# Microcontroller_Board.net
KiCad netlist of a schematic drawn in Altium Designer
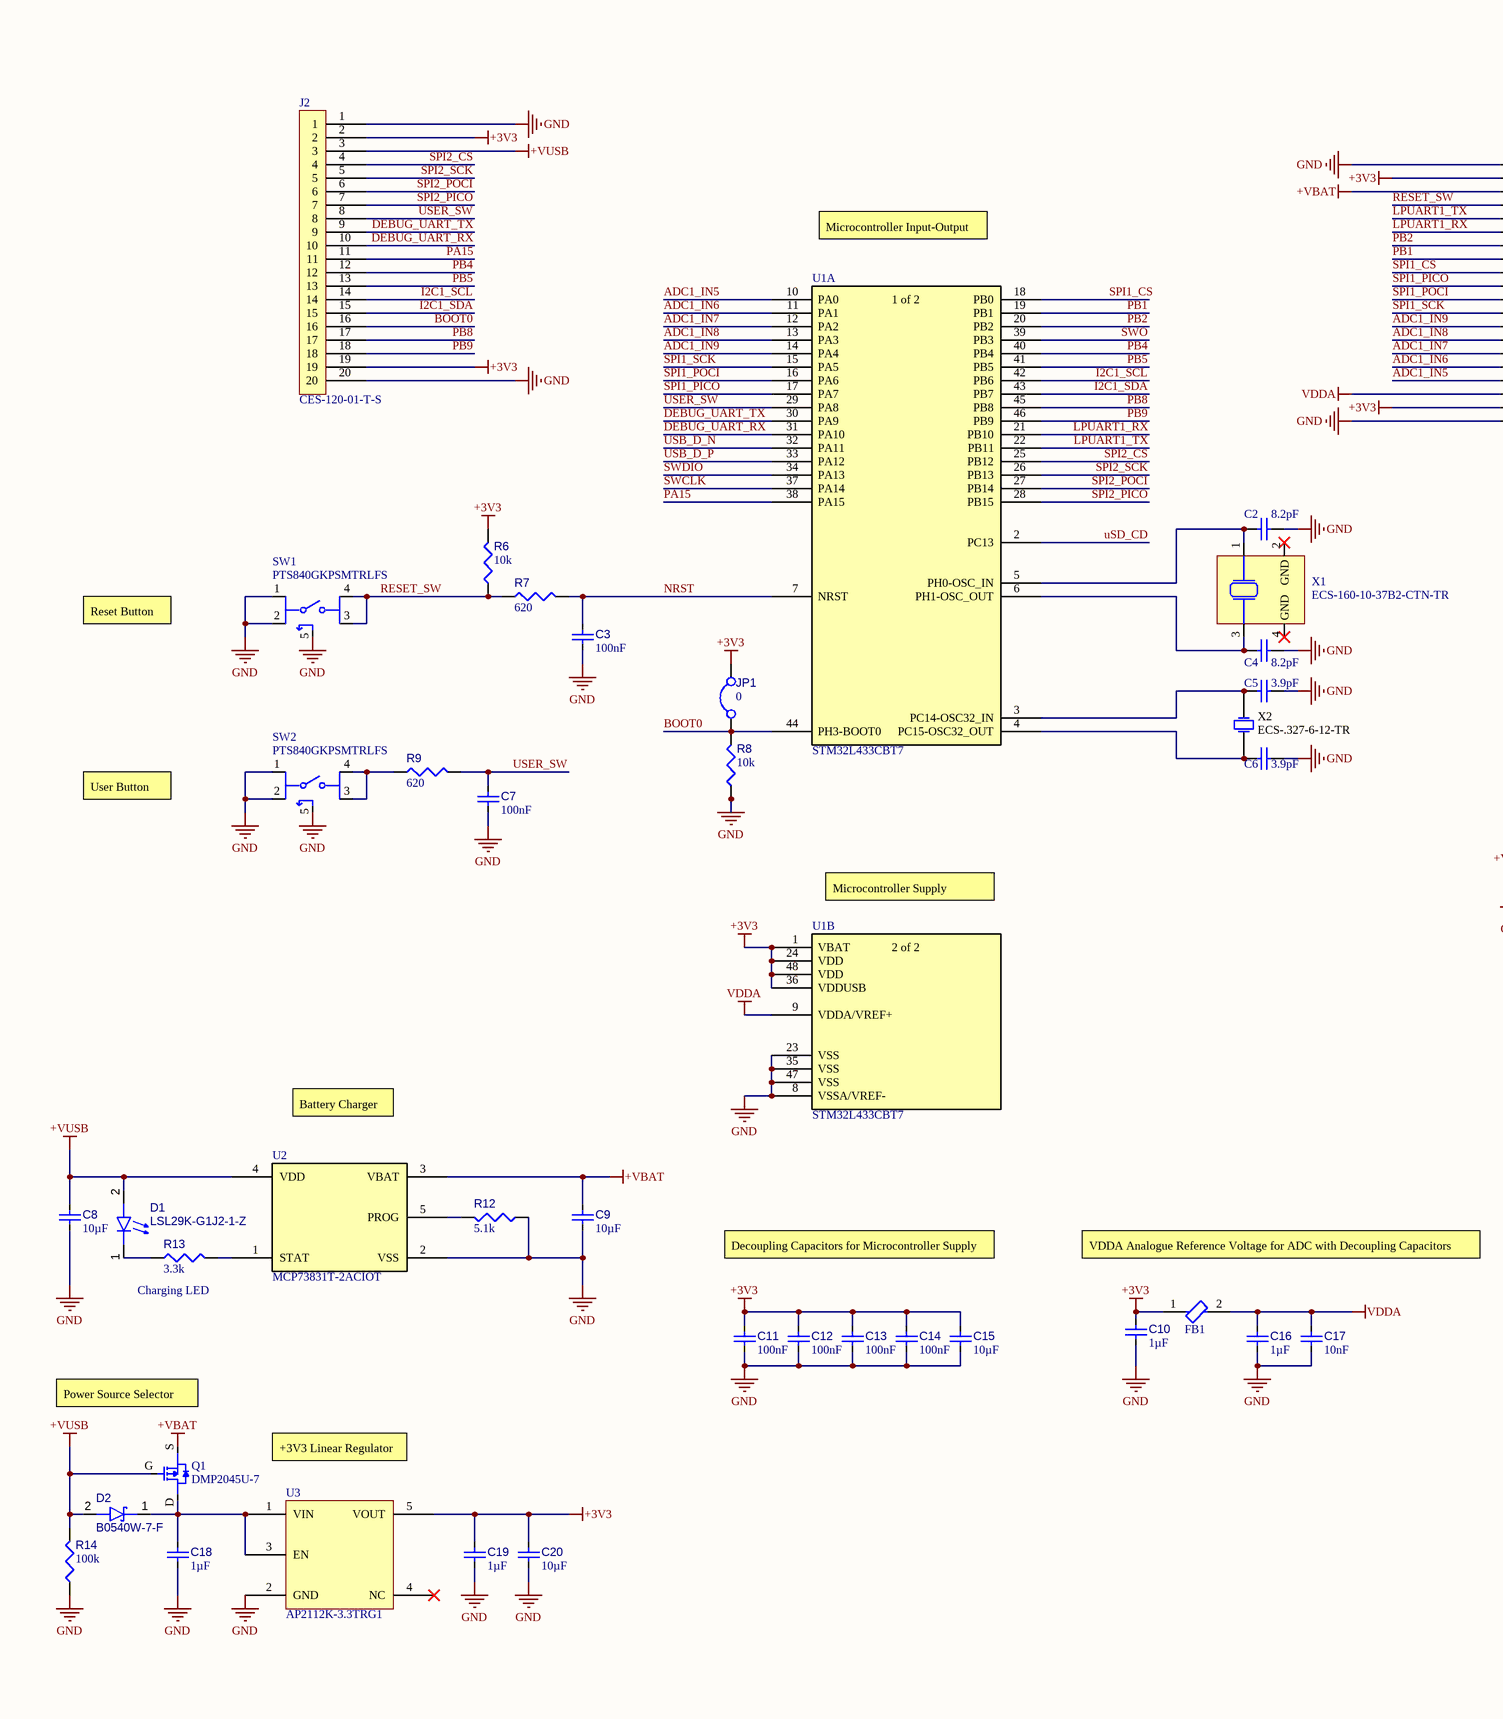
[diagram p0: Microcontroller Board.SchDoc, left]
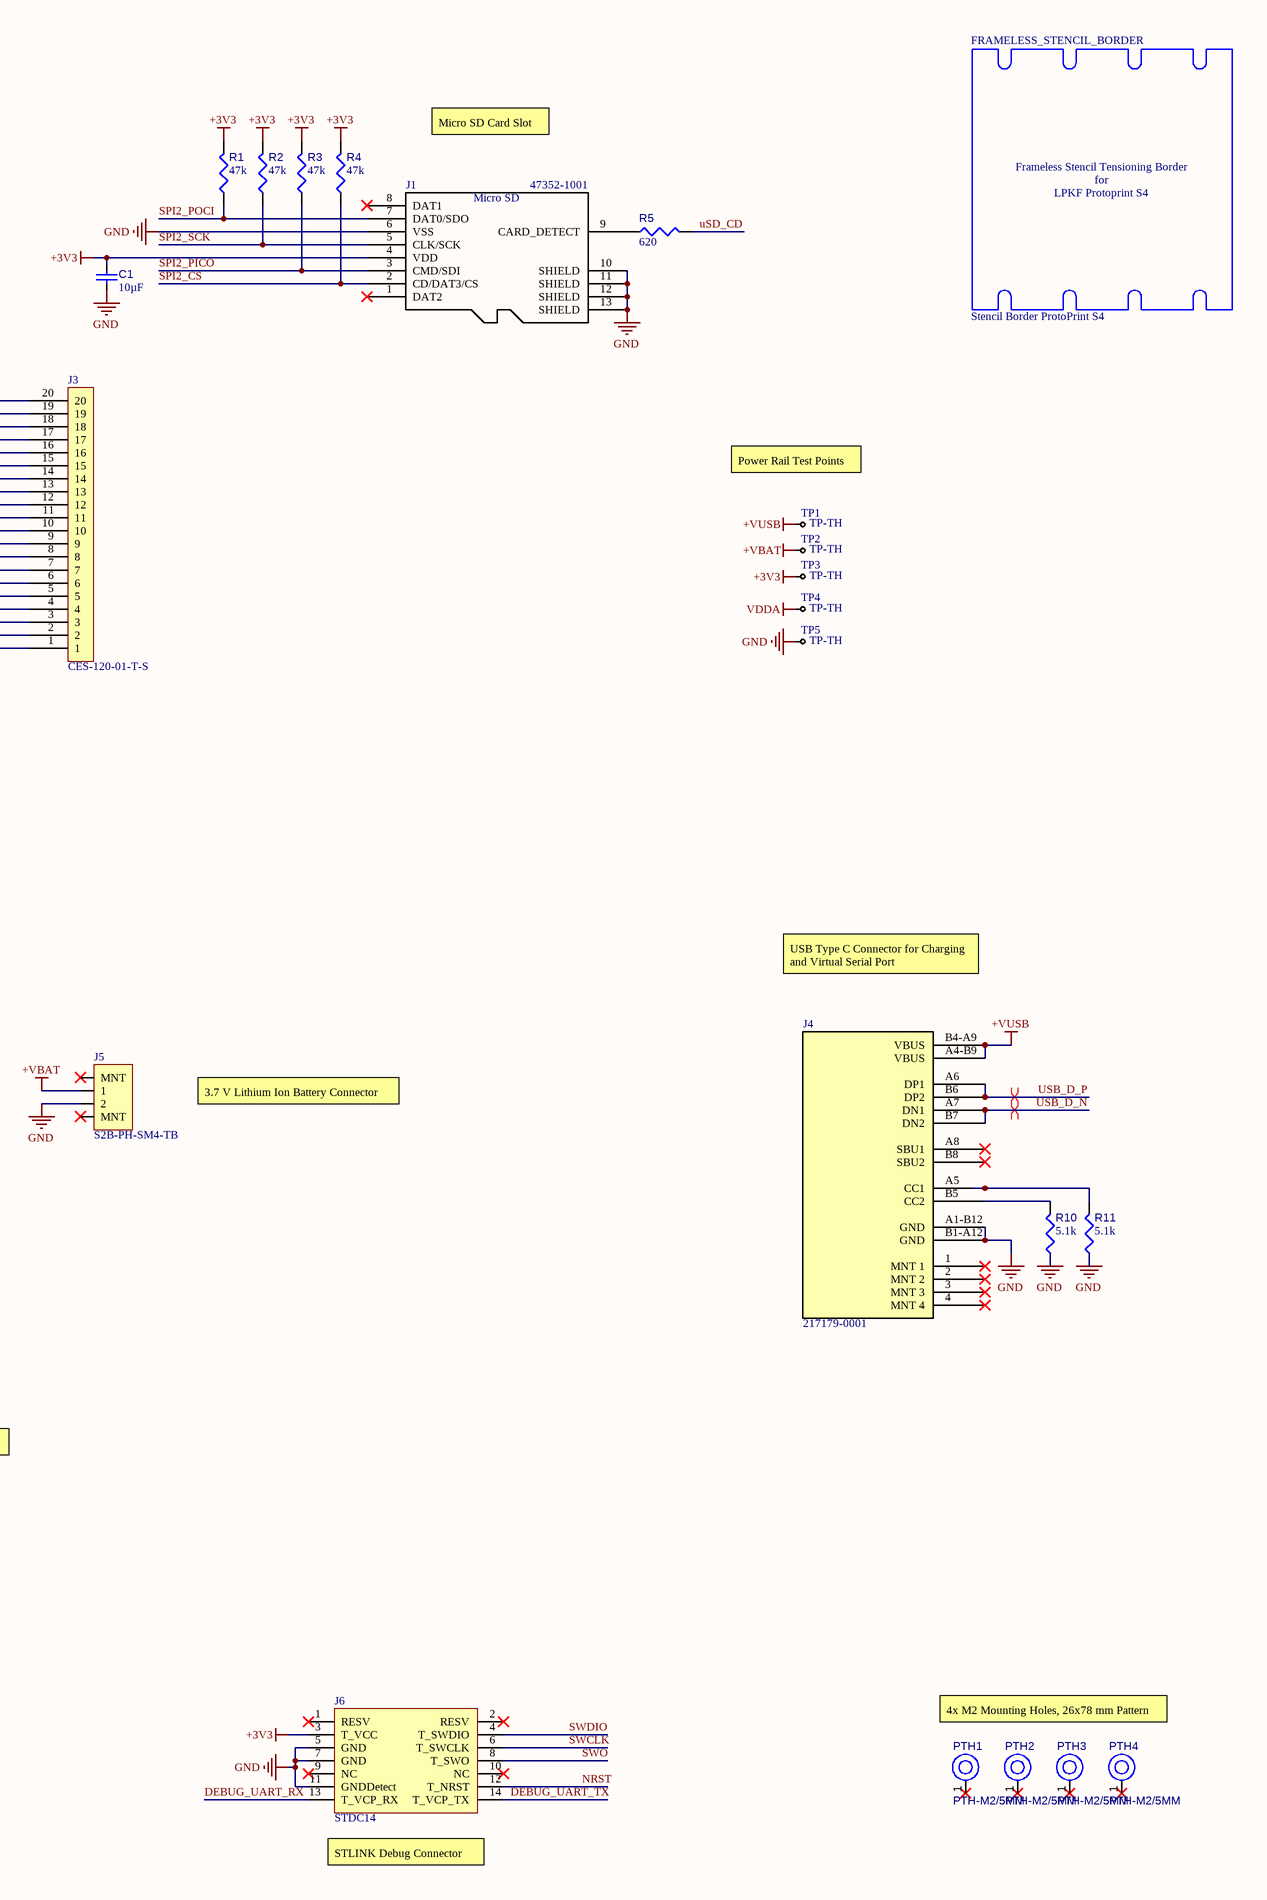
[diagram p1: Microcontroller Board.SchDoc, right]

(export (version "E")
  (design (tool "Eeschema 10.0.6"))
  (components
    (comp (ref "C1")
      (value "10µF")
      (footprint "CAPC1608X90X40ML10T20")
      (description "Chip Capacitor, 10 uF, +/-10%, 16 V, 0603(1608 Metric)")
      (fields (field (name "TOLERANCE") "10%") (field (name "Comment") "10 uF +/- 10% 16 V 0603"))
      (libsource (lib "Binar Space Program - Curtin University") (part "CAP-NP-2"))
    )
    (comp (ref "C2")
      (value "8.2pF")
      (footprint "CAPC1608X90X40NL10T20")
      (description "Chip Capacitor, 8.2 pF, 10%, 50 V, 0603 (1608 Metric)")
      (fields
        (field (name "TOLERANCE") "10%")
        (field (name "Comment") "Capacitor 8.2 pF 10% 50 V 0603")
        (field (name "CREATED BY") "Robert Howie")
      )
      (libsource (lib "") (part "CAP-NP-2_1"))
    )
    (comp (ref "C3")
      (value "100nF")
      (footprint "CAPC1608X90X40ML10T20")
      (description "Chip Capacitor, 100 nF, +/- 10%, 50 V, 0603 (1608 Metric)")
      (fields (field (name "TOLERANCE") "10%") (field (name "Comment") "Capacitor 100 nF +/-10% 50 V 0603"))
      (libsource (lib "Binar Space Program - Curtin University") (part "CAP-NP-2"))
    )
    (comp (ref "C4")
      (value "8.2pF")
      (footprint "CAPC1608X90X40NL10T20")
      (description "Chip Capacitor, 8.2 pF, 10%, 50 V, 0603 (1608 Metric)")
      (fields
        (field (name "TOLERANCE") "10%")
        (field (name "Comment") "Capacitor 8.2 pF 10% 50 V 0603")
        (field (name "CREATED BY") "Robert Howie")
      )
      (libsource (lib "") (part "CAP-NP-2_1"))
    )
    (comp (ref "C5")
      (value "3.9pF")
      (footprint "CAPC1608X90X40NL10T20")
      (description "Chip Capacitor, 3.9 pF, 10%, 50 V, 0603 (1608 Metric)")
      (fields
        (field (name "TOLERANCE") "10%")
        (field (name "Comment") "3.9 pF 10% 50 V 0603")
        (field (name "CREATED BY") "Robert Howie")
      )
      (libsource (lib "") (part "CAP-NP-2_1"))
    )
    (comp (ref "C6")
      (value "3.9pF")
      (footprint "CAPC1608X90X40NL10T20")
      (description "Chip Capacitor, 3.9 pF, 10%, 50 V, 0603 (1608 Metric)")
      (fields
        (field (name "TOLERANCE") "10%")
        (field (name "Comment") "3.9 pF 10% 50 V 0603")
        (field (name "CREATED BY") "Robert Howie")
      )
      (libsource (lib "") (part "CAP-NP-2_1"))
    )
    (comp (ref "C7")
      (value "100nF")
      (footprint "CAPC1608X90X40ML10T20")
      (description "Chip Capacitor, 100 nF, +/- 10%, 50 V, 0603 (1608 Metric)")
      (fields (field (name "TOLERANCE") "10%") (field (name "Comment") "Capacitor 100 nF +/-10% 50 V 0603"))
      (libsource (lib "Binar Space Program - Curtin University") (part "CAP-NP-2"))
    )
    (comp (ref "C8")
      (value "10µF")
      (footprint "CAPC1608X90X40ML10T20")
      (description "Chip Capacitor, 10 uF, +/-10%, 16 V, 0603(1608 Metric)")
      (fields (field (name "TOLERANCE") "10%") (field (name "Comment") "10 uF +/- 10% 16 V 0603"))
      (libsource (lib "Binar Space Program - Curtin University") (part "CAP-NP-2"))
    )
    (comp (ref "C9")
      (value "10µF")
      (footprint "CAPC1608X90X40ML10T20")
      (description "Chip Capacitor, 10 uF, +/-10%, 16 V, 0603(1608 Metric)")
      (fields (field (name "TOLERANCE") "10%") (field (name "Comment") "10 uF +/- 10% 16 V 0603"))
      (libsource (lib "Binar Space Program - Curtin University") (part "CAP-NP-2"))
    )
    (comp (ref "C10")
      (value "1µF")
      (footprint "CAPC1608X90X40ML10T20")
      (description "Chip Capacitor, 1 uF, +/-10%, 25 V, 0603(1608 Metric)")
      (fields (field (name "TOLERANCE") "10%") (field (name "Comment") "Capacitor 1 uF +/- 10% 25 V 0603"))
      (libsource (lib "Binar Space Program - Curtin University") (part "CAP-NP-2"))
    )
    (comp (ref "C11")
      (value "100nF")
      (footprint "CAPC1608X90X40ML10T20")
      (description "Chip Capacitor, 100 nF, +/- 10%, 50 V, 0603 (1608 Metric)")
      (fields (field (name "TOLERANCE") "10%") (field (name "Comment") "Capacitor 100 nF +/-10% 50 V 0603"))
      (libsource (lib "Binar Space Program - Curtin University") (part "CAP-NP-2"))
    )
    (comp (ref "C12")
      (value "100nF")
      (footprint "CAPC1608X90X40ML10T20")
      (description "Chip Capacitor, 100 nF, +/- 10%, 50 V, 0603 (1608 Metric)")
      (fields (field (name "TOLERANCE") "10%") (field (name "Comment") "Capacitor 100 nF +/-10% 50 V 0603"))
      (libsource (lib "Binar Space Program - Curtin University") (part "CAP-NP-2"))
    )
    (comp (ref "C13")
      (value "100nF")
      (footprint "CAPC1608X90X40ML10T20")
      (description "Chip Capacitor, 100 nF, +/- 10%, 50 V, 0603 (1608 Metric)")
      (fields (field (name "TOLERANCE") "10%") (field (name "Comment") "Capacitor 100 nF +/-10% 50 V 0603"))
      (libsource (lib "Binar Space Program - Curtin University") (part "CAP-NP-2"))
    )
    (comp (ref "C14")
      (value "100nF")
      (footprint "CAPC1608X90X40ML10T20")
      (description "Chip Capacitor, 100 nF, +/- 10%, 50 V, 0603 (1608 Metric)")
      (fields (field (name "TOLERANCE") "10%") (field (name "Comment") "Capacitor 100 nF +/-10% 50 V 0603"))
      (libsource (lib "Binar Space Program - Curtin University") (part "CAP-NP-2"))
    )
    (comp (ref "C15")
      (value "10µF")
      (footprint "CAPC1608X90X40ML10T20")
      (description "Chip Capacitor, 10 uF, +/-10%, 16 V, 0603(1608 Metric)")
      (fields (field (name "TOLERANCE") "10%") (field (name "Comment") "10 uF +/- 10% 16 V 0603"))
      (libsource (lib "Binar Space Program - Curtin University") (part "CAP-NP-2"))
    )
    (comp (ref "C16")
      (value "1µF")
      (footprint "CAPC1608X90X40ML10T20")
      (description "Chip Capacitor, 1 uF, +/-10%, 25 V, 0603(1608 Metric)")
      (fields (field (name "TOLERANCE") "10%") (field (name "Comment") "Capacitor 1 uF +/- 10% 25 V 0603"))
      (libsource (lib "Binar Space Program - Curtin University") (part "CAP-NP-2"))
    )
    (comp (ref "C17")
      (value "10nF")
      (footprint "CAPC1608X90X40ML10T20")
      (description "Chip Capacitor, 10 nF, +/- 10%, 50 V, 0603 (1608 Metric)")
      (fields
        (field (name "TOLERANCE") "10%")
        (field (name "Comment") "Capacitor 10 nF +/-10% 50 V 0603")
        (field (name "CREATED BY") "Robert Howie")
      )
      (libsource (lib "Binar Space Program - Curtin University") (part "CAP-NP-2"))
    )
    (comp (ref "C18")
      (value "1µF")
      (footprint "CAPC1608X90X40ML10T20")
      (description "Chip Capacitor, 1 uF, +/-10%, 25 V, 0603(1608 Metric)")
      (fields (field (name "TOLERANCE") "10%") (field (name "Comment") "Capacitor 1 uF +/- 10% 25 V 0603"))
      (libsource (lib "Binar Space Program - Curtin University") (part "CAP-NP-2"))
    )
    (comp (ref "C19")
      (value "1µF")
      (footprint "CAPC1608X90X40ML10T20")
      (description "Chip Capacitor, 1 uF, +/-10%, 25 V, 0603(1608 Metric)")
      (fields (field (name "TOLERANCE") "10%") (field (name "Comment") "Capacitor 1 uF +/- 10% 25 V 0603"))
      (libsource (lib "Binar Space Program - Curtin University") (part "CAP-NP-2"))
    )
    (comp (ref "C20")
      (value "10µF")
      (footprint "CAPC1608X90X40ML10T20")
      (description "Chip Capacitor, 10 uF, +/-10%, 16 V, 0603(1608 Metric)")
      (fields (field (name "TOLERANCE") "10%") (field (name "Comment") "10 uF +/- 10% 16 V 0603"))
      (libsource (lib "Binar Space Program - Curtin University") (part "CAP-NP-2"))
    )
    (comp (ref "D1")
      (value "LSL29K-G1J2-1-Z")
      (footprint "FP-LS_L29K-MFG")
      (description "LED Red, Diffused, 0603, 2mA")
      (libsource (lib "Binar Space Program - Curtin University") (part "DIODE-LED-2"))
    )
    (comp (ref "D2")
      (value "B0540W-7-F")
      (footprint "FP-SOD123-MFG")
      (description "Rectifier Diode, Schottky, 1 Phase, 1 Element, 0.5A, 40V V(RRM), Silicon")
      (libsource (lib "Binar Space Program - Curtin University") (part "D-SKY-KA2"))
    )
    (comp (ref "FB1")
      (value "LAMGL160808T471RD")
      (footprint "INDC1608X10M")
      (description "Ferrite Bead 0603 470ohm 25% AEC-Q200")
      (fields (field (name "TOLERANCE") "25%") (field (name "CREATED BY") "Robert Howie"))
      (libsource (lib "Binar Space Program - Curtin University") (part "5f30dd21d616792df468990f7003faa"))
    )
    (comp (ref "FRAMELESS_STENCIL_BORDER")
      (value "Stencil Border ProtoPrint S4")
      (footprint "Frameless Stencil Tensioning Border for LPKF ProtoPrint s4")
      (description "Frameless stencil tensioning border for LPKF ProtoPrint S4")
      (fields (field (name "CREATED BY") "Robert Howie"))
      (libsource (lib "Binar Space Program - Curtin University") (part "Frameless Stencil Tensioning Border for LPKF Protoprint S4"))
    )
    (comp (ref "J1")
      (value "47352-1001")
      (footprint "MOLX-473521001_V")
      (fields (field (name "CREATED BY") "Robert Howie"))
      (libsource (lib "Binar Space Program - Curtin University") (part "CN-SD-8-1SW-4S"))
    )
    (comp (ref "J2")
      (value "CES-120-01-T-S")
      (footprint "SAMTEC-CES-120-01-X-S")
      (fields (field (name "CREATED BY") "Robert Howie"))
      (libsource (lib "") (part "CES-120-01-T-S-Symbol-1_1"))
    )
    (comp (ref "J3")
      (value "CES-120-01-T-S")
      (footprint "SAMTEC-CES-120-01-X-S")
      (fields (field (name "CREATED BY") "Robert Howie"))
      (libsource (lib "Binar Space Program - Curtin University") (part "CES-120-01-T-S-Symbol-1"))
    )
    (comp (ref "J4")
      (value "217179-0001")
      (footprint "FP-217179-0001-MFG")
      (description "USB Type C - Connector, Top-mount SMT, 16pos")
      (fields (field (name "CREATED BY") "Robert Howie"))
      (libsource (lib "Binar Space Program - Curtin University") (part "5f86746d156db037abd23105bb3dbc5"))
    )
    (comp (ref "J5")
      (value "S2B-PH-SM4-TB")
      (footprint "JST- S2B-PH-SM4-TB(LF)(SN)-2_V")
      (description "Connector Header, PH Series, 2 Position, Side Entry, 2.00mm, Solder, Surface Mount, Natural")
      (libsource (lib "Binar Space Program - Curtin University") (part "S2BPHSM4TBLFSN-Symbol-1"))
    )
    (comp (ref "J6")
      (value "STDC14")
      (footprint "FP-FTSH-107-01-L-DV-K")
      (description "STDC14 for STLINK Programmer")
      (libsource (lib "Binar Space Program - Curtin University") (part "STDC14"))
    )
    (comp (ref "JP1")
      (value "0")
      (footprint "RESC1608X55X25ML10T15")
      (description "Jumper 0603")
      (libsource (lib "Binar Space Program - Curtin University") (part "JP"))
    )
    (comp (ref "PTH1")
      (value "PTH-M2/5MM")
      (footprint "PTH-M2")
      (description "M2 Clearance (2.2 mm) Plated Through Hole, 5mm Diameter Pad")
      (fields (field (name "CREATED BY") "Robert Howie"))
      (libsource (lib "Binar Space Program - Curtin University") (part "CMP-00028-00010-1"))
    )
    (comp (ref "PTH2")
      (value "PTH-M2/5MM")
      (footprint "PTH-M2")
      (description "M2 Clearance (2.2 mm) Plated Through Hole, 5mm Diameter Pad")
      (fields (field (name "CREATED BY") "Robert Howie"))
      (libsource (lib "Binar Space Program - Curtin University") (part "CMP-00028-00010-1"))
    )
    (comp (ref "PTH3")
      (value "PTH-M2/5MM")
      (footprint "PTH-M2")
      (description "M2 Clearance (2.2 mm) Plated Through Hole, 5mm Diameter Pad")
      (fields (field (name "CREATED BY") "Robert Howie"))
      (libsource (lib "Binar Space Program - Curtin University") (part "CMP-00028-00010-1"))
    )
    (comp (ref "PTH4")
      (value "PTH-M2/5MM")
      (footprint "PTH-M2")
      (description "M2 Clearance (2.2 mm) Plated Through Hole, 5mm Diameter Pad")
      (fields (field (name "CREATED BY") "Robert Howie"))
      (libsource (lib "Binar Space Program - Curtin University") (part "CMP-00028-00010-1"))
    )
    (comp (ref "Q1")
      (value "DMP2045U-7")
      (footprint "SOT90P235X110-3M")
      (libsource (lib "Binar Space Program - Curtin University") (part "P-CH"))
    )
    (comp (ref "R1")
      (value "47k")
      (footprint "RESC1608X55X25ML10T15")
      (description "Chip Resistor, 47 KOhm, +/- 1%, 01 W, -55 to 155 degC, 0603 (1608 Metric)")
      (fields
        (field (name "TOLERANCE") "1%")
        (field (name "POWER") "100mW")
        (field (name "CREATED BY") "Robert Howie")
      )
      (libsource (lib "Binar Space Program - Curtin University") (part "RES-2"))
    )
    (comp (ref "R2")
      (value "47k")
      (footprint "RESC1608X55X25ML10T15")
      (description "Chip Resistor, 47 KOhm, +/- 1%, 01 W, -55 to 155 degC, 0603 (1608 Metric)")
      (fields
        (field (name "TOLERANCE") "1%")
        (field (name "POWER") "100mW")
        (field (name "CREATED BY") "Robert Howie")
      )
      (libsource (lib "Binar Space Program - Curtin University") (part "RES-2"))
    )
    (comp (ref "R3")
      (value "47k")
      (footprint "RESC1608X55X25ML10T15")
      (description "Chip Resistor, 47 KOhm, +/- 1%, 01 W, -55 to 155 degC, 0603 (1608 Metric)")
      (fields
        (field (name "TOLERANCE") "1%")
        (field (name "POWER") "100mW")
        (field (name "CREATED BY") "Robert Howie")
      )
      (libsource (lib "Binar Space Program - Curtin University") (part "RES-2"))
    )
    (comp (ref "R4")
      (value "47k")
      (footprint "RESC1608X55X25ML10T15")
      (description "Chip Resistor, 47 KOhm, +/- 1%, 01 W, -55 to 155 degC, 0603 (1608 Metric)")
      (fields
        (field (name "TOLERANCE") "1%")
        (field (name "POWER") "100mW")
        (field (name "CREATED BY") "Robert Howie")
      )
      (libsource (lib "Binar Space Program - Curtin University") (part "RES-2"))
    )
    (comp (ref "R5")
      (value "620")
      (footprint "RESC1608X55X25ML10T15")
      (description "Chip Resistor, 620 Ohm, +/-1%, 0.1 W, -55 to 155 degC, 0603 (1608 Metric)")
      (fields
        (field (name "TOLERANCE") "1%")
        (field (name "POWER") "100mW")
        (field (name "CREATED BY") "Robert Howie")
      )
      (libsource (lib "Binar Space Program - Curtin University") (part "RES-2"))
    )
    (comp (ref "R6")
      (value "10k")
      (footprint "RESC1608X55X25ML10T15")
      (description "Chip Resistor, 10 KOhm, +/- 1%, 01 W, -55 to 155 degC, 0603 (1608 Metric)")
      (fields (field (name "TOLERANCE") "1%") (field (name "POWER") "100mW"))
      (libsource (lib "Binar Space Program - Curtin University") (part "RES-2"))
    )
    (comp (ref "R7")
      (value "620")
      (footprint "RESC1608X55X25ML10T15")
      (description "Chip Resistor, 620 Ohm, +/-1%, 0.1 W, -55 to 155 degC, 0603 (1608 Metric)")
      (fields
        (field (name "TOLERANCE") "1%")
        (field (name "POWER") "100mW")
        (field (name "CREATED BY") "Robert Howie")
      )
      (libsource (lib "Binar Space Program - Curtin University") (part "RES-2"))
    )
    (comp (ref "R8")
      (value "10k")
      (footprint "RESC1608X55X25ML10T15")
      (description "Chip Resistor, 10 KOhm, +/- 1%, 01 W, -55 to 155 degC, 0603 (1608 Metric)")
      (fields (field (name "TOLERANCE") "1%") (field (name "POWER") "100mW"))
      (libsource (lib "Binar Space Program - Curtin University") (part "RES-2"))
    )
    (comp (ref "R9")
      (value "620")
      (footprint "RESC1608X55X25ML10T15")
      (description "Chip Resistor, 620 Ohm, +/-1%, 0.1 W, -55 to 155 degC, 0603 (1608 Metric)")
      (fields
        (field (name "TOLERANCE") "1%")
        (field (name "POWER") "100mW")
        (field (name "CREATED BY") "Robert Howie")
      )
      (libsource (lib "Binar Space Program - Curtin University") (part "RES-2"))
    )
    (comp (ref "R10")
      (value "5.1k")
      (footprint "RESC1608X55X25ML10T15")
      (description "Chip Resistor, 5.1 KOhm, +/- 1%, 0.1 W, -55 to 155 degC, 0603 (1608 Metric)")
      (fields
        (field (name "TOLERANCE") "1%")
        (field (name "POWER") "100mW")
        (field (name "CREATED BY") "Robert Howie")
      )
      (libsource (lib "Binar Space Program - Curtin University") (part "RES-2"))
    )
    (comp (ref "R11")
      (value "5.1k")
      (footprint "RESC1608X55X25ML10T15")
      (description "Chip Resistor, 5.1 KOhm, +/- 1%, 0.1 W, -55 to 155 degC, 0603 (1608 Metric)")
      (fields
        (field (name "TOLERANCE") "1%")
        (field (name "POWER") "100mW")
        (field (name "CREATED BY") "Robert Howie")
      )
      (libsource (lib "Binar Space Program - Curtin University") (part "RES-2"))
    )
    (comp (ref "R12")
      (value "5.1k")
      (footprint "RESC1608X55X25ML10T15")
      (description "Chip Resistor, 5.1 KOhm, +/- 1%, 0.1 W, -55 to 155 degC, 0603 (1608 Metric)")
      (fields
        (field (name "TOLERANCE") "1%")
        (field (name "POWER") "100mW")
        (field (name "CREATED BY") "Robert Howie")
      )
      (libsource (lib "Binar Space Program - Curtin University") (part "RES-2"))
    )
    (comp (ref "R13")
      (value "3.3k")
      (footprint "RESC1608X55X25ML10T15")
      (description "Chip Resistor, 3.3 kOhm, +/- 1%, 100 mW, -55 to 155 degC, 0603 (1608 Metric)")
      (fields (field (name "POWER") "100mW") (field (name "TOLERANCE") "1%"))
      (libsource (lib "Binar Space Program - Curtin University") (part "RES-2"))
    )
    (comp (ref "R14")
      (value "100k")
      (footprint "RESC1608X55X25ML10T15")
      (description "Chip Resistor, 100 KOhm, +/- 1%, 0.1 W, -55 to 155 degC, 0603 (1608 Metric)")
      (fields
        (field (name "POWER") "100mW")
        (field (name "TOLERANCE") "1%")
        (field (name "CREATED BY") "Robert Howie")
      )
      (libsource (lib "Binar Space Program - Curtin University") (part "RES-2"))
    )
    (comp (ref "SW1")
      (value "PTS840GKPSMTRLFS")
      (footprint "FP-PTS840_GKP_SMTR_LFS-MFG")
      (fields (field (name "CREATED BY") "Robert Howie"))
      (libsource (lib "Binar Space Program - Curtin University") (part "1adf0dd01260c80cf25a44bfd6b99ba"))
    )
    (comp (ref "SW2")
      (value "PTS840GKPSMTRLFS")
      (footprint "FP-PTS840_GKP_SMTR_LFS-MFG")
      (fields (field (name "CREATED BY") "Robert Howie"))
      (libsource (lib "Binar Space Program - Curtin University") (part "1adf0dd01260c80cf25a44bfd6b99ba"))
    )
    (comp (ref "TP1")
      (value "TP-TH")
      (footprint "1 Pin Header Strip Footprint")
      (description "Throughole Test Point")
      (fields (field (name "CREATED BY") "Robert Howie"))
      (libsource (lib "Binar Space Program - Curtin University") (part "CMP-001-0001-5"))
    )
    (comp (ref "TP2")
      (value "TP-TH")
      (footprint "1 Pin Header Strip Footprint")
      (description "Throughole Test Point")
      (fields (field (name "CREATED BY") "Robert Howie"))
      (libsource (lib "Binar Space Program - Curtin University") (part "CMP-001-0001-5"))
    )
    (comp (ref "TP3")
      (value "TP-TH")
      (footprint "1 Pin Header Strip Footprint")
      (description "Throughole Test Point")
      (fields (field (name "CREATED BY") "Robert Howie"))
      (libsource (lib "Binar Space Program - Curtin University") (part "CMP-001-0001-5"))
    )
    (comp (ref "TP4")
      (value "TP-TH")
      (footprint "1 Pin Header Strip Footprint")
      (description "Throughole Test Point")
      (fields (field (name "CREATED BY") "Robert Howie"))
      (libsource (lib "Binar Space Program - Curtin University") (part "CMP-001-0001-5"))
    )
    (comp (ref "TP5")
      (value "TP-TH")
      (footprint "1 Pin Header Strip Footprint")
      (description "Throughole Test Point")
      (fields (field (name "CREATED BY") "Robert Howie"))
      (libsource (lib "Binar Space Program - Curtin University") (part "CMP-001-0001-5"))
    )
    (comp (ref "U1")
      (value "STM32L433CBT7")
      (footprint "LQFP48-7x7mm")
      (description "Ultra-low-power with FPU Arm Cortex-M4 MCU 80 MHz with 128 Kbytes of Flash memory, USB FS, LCD")
      (fields (field (name "CREATED BY") "Robert Howie"))
      (libsource (lib "Binar Space Program - Curtin University") (part "STM32L433CBT7"))
    )
    (comp (ref "U2")
      (value "MCP73831T-2ACIOT")
      (footprint "SOT-23-5_MC_MCH-M")
      (description "Single Cell, Li-Ion/Li-Polymer Charge Management Controller")
      (fields
        (field (name "MANUFACTURER_PART_NUMBER") "MCP73831T-2ACI/OT")
        (field (name "CREATED BY") "Robert Howie")
        (field (name "COPYRIGHT") "Copyright (C) 2023 Ultra Librarian. All rights reserved.")
      )
      (libsource (lib "Binar Space Program - Curtin University") (part "MCP73831T-2ACIOT"))
    )
    (comp (ref "U3")
      (value "AP2112K-3.3TRG1")
      (footprint "SOT-23-5")
      (description "Fixed Positive LDO Regulator, 3.3V, 0.4V Dropout, CMOS, PDSO5")
      (libsource (lib "Binar Space Program - Curtin University") (part "AP2112K-3.3TRG1-Symbol-1"))
    )
    (comp (ref "X1")
      (value "ECS-160-10-37B2-CTN-TR")
      (footprint "DFN135P200X50-4N")
      (description "Crystal 16MHz 10pF 4-Pin SMD ECX-1637B2 T/R")
      (libsource (lib "Binar Space Program - Curtin University") (part "CMP-003-00030-3"))
    )
    (comp (ref "X2")
      (value "ECS-.327-6-12-TR")
      (footprint "DFN120P200X60-2N")
      (description "Parallel - Fundamental Quartz Crystal, 0.032768MHz Nom")
      (libsource (lib "Binar Space Program - Curtin University") (part "XTAL-2"))
    )
  )
  (nets
    (net (code "1") (name "+3V3") (class "Default")
      (node (ref "C1") (pin "2") (pinfunction "2_2") (pintype "passive"))
      (node (ref "C10") (pin "2") (pinfunction "2_2") (pintype "passive"))
      (node (ref "C11") (pin "2") (pinfunction "2_2") (pintype "passive"))
      (node (ref "C12") (pin "2") (pinfunction "2_2") (pintype "passive"))
      (node (ref "C13") (pin "2") (pinfunction "2_2") (pintype "passive"))
      (node (ref "C14") (pin "2") (pinfunction "2_2") (pintype "passive"))
      (node (ref "C15") (pin "2") (pinfunction "2_2") (pintype "passive"))
      (node (ref "C19") (pin "2") (pinfunction "2_2") (pintype "passive"))
      (node (ref "C20") (pin "2") (pinfunction "2_2") (pintype "passive"))
      (node (ref "FB1") (pin "1") (pinfunction "1_1") (pintype "passive"))
      (node (ref "J1") (pin "4") (pinfunction "VDD_4") (pintype "passive"))
      (node (ref "J2") (pin "19") (pinfunction "19_19") (pintype "passive"))
      (node (ref "J2") (pin "2") (pinfunction "2_2") (pintype "passive"))
      (node (ref "J3") (pin "19") (pinfunction "19_19") (pintype "passive"))
      (node (ref "J3") (pin "2") (pinfunction "2_2") (pintype "passive"))
      (node (ref "J6") (pin "3") (pinfunction "T_VCC_3") (pintype "passive"))
      (node (ref "JP1") (pin "2") (pinfunction "2_2") (pintype "passive"))
      (node (ref "R1") (pin "2") (pinfunction "2_2") (pintype "passive"))
      (node (ref "R2") (pin "2") (pinfunction "2_2") (pintype "passive"))
      (node (ref "R3") (pin "2") (pinfunction "2_2") (pintype "passive"))
      (node (ref "R4") (pin "2") (pinfunction "2_2") (pintype "passive"))
      (node (ref "R6") (pin "2") (pinfunction "2_2") (pintype "passive"))
      (node (ref "TP3") (pin "1") (pinfunction "TP_1") (pintype "passive"))
      (node (ref "U1") (pin "1") (pinfunction "VBAT_1") (pintype "passive"))
      (node (ref "U1") (pin "24") (pinfunction "VDD_24") (pintype "passive"))
      (node (ref "U1") (pin "36") (pinfunction "VDDUSB_36") (pintype "passive"))
      (node (ref "U1") (pin "48") (pinfunction "VDD_48") (pintype "passive"))
      (node (ref "U3") (pin "5") (pinfunction "VOUT_5") (pintype "passive"))
    )
    (net (code "2") (name "+VBAT") (class "Default")
      (node (ref "C9") (pin "2") (pinfunction "2_2") (pintype "passive"))
      (node (ref "J3") (pin "18") (pinfunction "18_18") (pintype "passive"))
      (node (ref "J5") (pin "1") (pinfunction "1_1") (pintype "passive"))
      (node (ref "Q1") (pin "S") (pinfunction "S_S") (pintype "passive"))
      (node (ref "TP2") (pin "1") (pinfunction "TP_1") (pintype "passive"))
      (node (ref "U2") (pin "3") (pinfunction "VBAT_3") (pintype "passive"))
    )
    (net (code "3") (name "+VUSB") (class "Default")
      (node (ref "C8") (pin "2") (pinfunction "2_2") (pintype "passive"))
      (node (ref "D1") (pin "2") (pinfunction "A_2") (pintype "passive"))
      (node (ref "D2") (pin "2") (pinfunction "A_2") (pintype "passive"))
      (node (ref "J2") (pin "3") (pinfunction "3_3") (pintype "passive"))
      (node (ref "J4") (pin "A4-B9") (pinfunction "VBUS_A4-B9") (pintype "power_in"))
      (node (ref "J4") (pin "B4-A9") (pinfunction "VBUS_B4-A9") (pintype "power_in"))
      (node (ref "Q1") (pin "G") (pinfunction "G_G") (pintype "passive"))
      (node (ref "R14") (pin "2") (pinfunction "2_2") (pintype "passive"))
      (node (ref "TP1") (pin "1") (pinfunction "TP_1") (pintype "passive"))
      (node (ref "U2") (pin "4") (pinfunction "VDD_4") (pintype "passive"))
    )
    (net (code "4") (name "/ADC1_IN5") (class "Default")
      (node (ref "J3") (pin "4") (pinfunction "4_4") (pintype "passive"))
      (node (ref "U1") (pin "10") (pinfunction "PA0_10") (pintype "passive"))
    )
    (net (code "5") (name "/ADC1_IN6") (class "Default")
      (node (ref "J3") (pin "5") (pinfunction "5_5") (pintype "passive"))
      (node (ref "U1") (pin "11") (pinfunction "PA1_11") (pintype "passive"))
    )
    (net (code "6") (name "/ADC1_IN7") (class "Default")
      (node (ref "J3") (pin "6") (pinfunction "6_6") (pintype "passive"))
      (node (ref "U1") (pin "12") (pinfunction "PA2_12") (pintype "passive"))
    )
    (net (code "7") (name "/ADC1_IN8") (class "Default")
      (node (ref "J3") (pin "7") (pinfunction "7_7") (pintype "passive"))
      (node (ref "U1") (pin "13") (pinfunction "PA3_13") (pintype "passive"))
    )
    (net (code "8") (name "/ADC1_IN9") (class "Default")
      (node (ref "J3") (pin "8") (pinfunction "8_8") (pintype "passive"))
      (node (ref "U1") (pin "14") (pinfunction "PA4_14") (pintype "passive"))
    )
    (net (code "9") (name "/BOOT0") (class "Default")
      (node (ref "J2") (pin "16") (pinfunction "16_16") (pintype "passive"))
      (node (ref "JP1") (pin "1") (pinfunction "1_1") (pintype "passive"))
      (node (ref "R8") (pin "2") (pinfunction "2_2") (pintype "passive"))
      (node (ref "U1") (pin "44") (pinfunction "PH3-BOOT0_44") (pintype "passive"))
    )
    (net (code "10") (name "/DEBUG_UART_RX") (class "Default")
      (node (ref "J2") (pin "10") (pinfunction "10_10") (pintype "passive"))
      (node (ref "J6") (pin "13") (pinfunction "T_VCP_RX_13") (pintype "passive"))
      (node (ref "U1") (pin "31") (pinfunction "PA10_31") (pintype "passive"))
    )
    (net (code "11") (name "/DEBUG_UART_TX") (class "Default")
      (node (ref "J2") (pin "9") (pinfunction "9_9") (pintype "passive"))
      (node (ref "J6") (pin "14") (pinfunction "T_VCP_TX_14") (pintype "passive"))
      (node (ref "U1") (pin "30") (pinfunction "PA9_30") (pintype "passive"))
    )
    (net (code "12") (name "/I2C1_SCL") (class "Default")
      (node (ref "J2") (pin "14") (pinfunction "14_14") (pintype "passive"))
      (node (ref "U1") (pin "42") (pinfunction "PB6_42") (pintype "passive"))
    )
    (net (code "13") (name "/I2C1_SDA") (class "Default")
      (node (ref "J2") (pin "15") (pinfunction "15_15") (pintype "passive"))
      (node (ref "U1") (pin "43") (pinfunction "PB7_43") (pintype "passive"))
    )
    (net (code "14") (name "/LPUART1_RX") (class "Default")
      (node (ref "J3") (pin "15") (pinfunction "15_15") (pintype "passive"))
      (node (ref "U1") (pin "21") (pinfunction "PB10_21") (pintype "passive"))
    )
    (net (code "15") (name "/LPUART1_TX") (class "Default")
      (node (ref "J3") (pin "16") (pinfunction "16_16") (pintype "passive"))
      (node (ref "U1") (pin "22") (pinfunction "PB11_22") (pintype "passive"))
    )
    (net (code "16") (name "/NRST") (class "Default")
      (node (ref "C3") (pin "2") (pinfunction "2_2") (pintype "passive"))
      (node (ref "J6") (pin "12") (pinfunction "T_NRST_12") (pintype "passive"))
      (node (ref "R7") (pin "2") (pinfunction "2_2") (pintype "passive"))
      (node (ref "U1") (pin "7") (pinfunction "NRST_7") (pintype "passive"))
    )
    (net (code "17") (name "/PA15") (class "Default")
      (node (ref "J2") (pin "11") (pinfunction "11_11") (pintype "passive"))
      (node (ref "U1") (pin "38") (pinfunction "PA15_38") (pintype "passive"))
    )
    (net (code "18") (name "/PB1") (class "Default")
      (node (ref "J3") (pin "13") (pinfunction "13_13") (pintype "passive"))
      (node (ref "U1") (pin "19") (pinfunction "PB1_19") (pintype "passive"))
    )
    (net (code "19") (name "/PB2") (class "Default")
      (node (ref "J3") (pin "14") (pinfunction "14_14") (pintype "passive"))
      (node (ref "U1") (pin "20") (pinfunction "PB2_20") (pintype "passive"))
    )
    (net (code "20") (name "/PB4") (class "Default")
      (node (ref "J2") (pin "12") (pinfunction "12_12") (pintype "passive"))
      (node (ref "U1") (pin "40") (pinfunction "PB4_40") (pintype "passive"))
    )
    (net (code "21") (name "/PB5") (class "Default")
      (node (ref "J2") (pin "13") (pinfunction "13_13") (pintype "passive"))
      (node (ref "U1") (pin "41") (pinfunction "PB5_41") (pintype "passive"))
    )
    (net (code "22") (name "/PB8") (class "Default")
      (node (ref "J2") (pin "17") (pinfunction "17_17") (pintype "passive"))
      (node (ref "U1") (pin "45") (pinfunction "PB8_45") (pintype "passive"))
    )
    (net (code "23") (name "/PB9") (class "Default")
      (node (ref "J2") (pin "18") (pinfunction "18_18") (pintype "passive"))
      (node (ref "U1") (pin "46") (pinfunction "PB9_46") (pintype "passive"))
    )
    (net (code "24") (name "/RESET_SW") (class "Default")
      (node (ref "J3") (pin "17") (pinfunction "17_17") (pintype "passive"))
      (node (ref "R6") (pin "1") (pinfunction "1_1") (pintype "passive"))
      (node (ref "R7") (pin "1") (pinfunction "1_1") (pintype "passive"))
      (node (ref "SW1") (pin "3") (pinfunction "3_3") (pintype "passive"))
      (node (ref "SW1") (pin "4") (pinfunction "4_4") (pintype "passive"))
    )
    (net (code "25") (name "/SPI1_CS") (class "Default")
      (node (ref "J3") (pin "12") (pinfunction "12_12") (pintype "passive"))
      (node (ref "U1") (pin "18") (pinfunction "PB0_18") (pintype "passive"))
    )
    (net (code "26") (name "/SPI1_PICO") (class "Default")
      (node (ref "J3") (pin "11") (pinfunction "11_11") (pintype "passive"))
      (node (ref "U1") (pin "17") (pinfunction "PA7_17") (pintype "passive"))
    )
    (net (code "27") (name "/SPI1_POCI") (class "Default")
      (node (ref "J3") (pin "10") (pinfunction "10_10") (pintype "passive"))
      (node (ref "U1") (pin "16") (pinfunction "PA6_16") (pintype "passive"))
    )
    (net (code "28") (name "/SPI1_SCK") (class "Default")
      (node (ref "J3") (pin "9") (pinfunction "9_9") (pintype "passive"))
      (node (ref "U1") (pin "15") (pinfunction "PA5_15") (pintype "passive"))
    )
    (net (code "29") (name "/SPI2_CS") (class "Default")
      (node (ref "J1") (pin "2") (pinfunction "CD/DAT3/CS_2") (pintype "passive"))
      (node (ref "J2") (pin "4") (pinfunction "4_4") (pintype "passive"))
      (node (ref "R4") (pin "1") (pinfunction "1_1") (pintype "passive"))
      (node (ref "U1") (pin "25") (pinfunction "PB12_25") (pintype "passive"))
    )
    (net (code "30") (name "/SPI2_PICO") (class "Default")
      (node (ref "J1") (pin "3") (pinfunction "CMD/SDI_3") (pintype "passive"))
      (node (ref "J2") (pin "7") (pinfunction "7_7") (pintype "passive"))
      (node (ref "R3") (pin "1") (pinfunction "1_1") (pintype "passive"))
      (node (ref "U1") (pin "28") (pinfunction "PB15_28") (pintype "passive"))
    )
    (net (code "31") (name "/SPI2_POCI") (class "Default")
      (node (ref "J1") (pin "7") (pinfunction "DAT0/SDO_7") (pintype "passive"))
      (node (ref "J2") (pin "6") (pinfunction "6_6") (pintype "passive"))
      (node (ref "R1") (pin "1") (pinfunction "1_1") (pintype "passive"))
      (node (ref "U1") (pin "27") (pinfunction "PB14_27") (pintype "passive"))
    )
    (net (code "32") (name "/SPI2_SCK") (class "Default")
      (node (ref "J1") (pin "5") (pinfunction "CLK/SCK_5") (pintype "passive"))
      (node (ref "J2") (pin "5") (pinfunction "5_5") (pintype "passive"))
      (node (ref "R2") (pin "1") (pinfunction "1_1") (pintype "passive"))
      (node (ref "U1") (pin "26") (pinfunction "PB13_26") (pintype "passive"))
    )
    (net (code "33") (name "/SWCLK") (class "Default")
      (node (ref "J6") (pin "6") (pinfunction "T_SWCLK_6") (pintype "passive"))
      (node (ref "U1") (pin "37") (pinfunction "PA14_37") (pintype "passive"))
    )
    (net (code "34") (name "/SWDIO") (class "Default")
      (node (ref "J6") (pin "4") (pinfunction "T_SWDIO_4") (pintype "passive"))
      (node (ref "U1") (pin "34") (pinfunction "PA13_34") (pintype "passive"))
    )
    (net (code "35") (name "/SWO") (class "Default")
      (node (ref "J6") (pin "8") (pinfunction "T_SWO_8") (pintype "passive"))
      (node (ref "U1") (pin "39") (pinfunction "PB3_39") (pintype "passive"))
    )
    (net (code "36") (name "/USB_D_N") (class "Default")
      (node (ref "J4") (pin "A7") (pinfunction "DN1_A7") (pintype "passive"))
      (node (ref "J4") (pin "B7") (pinfunction "DN2_B7") (pintype "passive"))
      (node (ref "U1") (pin "32") (pinfunction "PA11_32") (pintype "passive"))
    )
    (net (code "37") (name "/USB_D_P") (class "Default")
      (node (ref "J4") (pin "A6") (pinfunction "DP1_A6") (pintype "passive"))
      (node (ref "J4") (pin "B6") (pinfunction "DP2_B6") (pintype "passive"))
      (node (ref "U1") (pin "33") (pinfunction "PA12_33") (pintype "passive"))
    )
    (net (code "38") (name "/USER_SW") (class "Default")
      (node (ref "C7") (pin "2") (pinfunction "2_2") (pintype "passive"))
      (node (ref "J2") (pin "8") (pinfunction "8_8") (pintype "passive"))
      (node (ref "R9") (pin "2") (pinfunction "2_2") (pintype "passive"))
      (node (ref "U1") (pin "29") (pinfunction "PA8_29") (pintype "passive"))
    )
    (net (code "39") (name "/uSD_CD") (class "Default")
      (node (ref "R5") (pin "2") (pinfunction "2_2") (pintype "passive"))
      (node (ref "U1") (pin "2") (pinfunction "PC13_2") (pintype "passive"))
    )
    (net (code "40") (name "GND") (class "Default")
      (node (ref "C1") (pin "1") (pinfunction "1_1") (pintype "passive"))
      (node (ref "C10") (pin "1") (pinfunction "1_1") (pintype "passive"))
      (node (ref "C11") (pin "1") (pinfunction "1_1") (pintype "passive"))
      (node (ref "C12") (pin "1") (pinfunction "1_1") (pintype "passive"))
      (node (ref "C13") (pin "1") (pinfunction "1_1") (pintype "passive"))
      (node (ref "C14") (pin "1") (pinfunction "1_1") (pintype "passive"))
      (node (ref "C15") (pin "1") (pinfunction "1_1") (pintype "passive"))
      (node (ref "C16") (pin "1") (pinfunction "1_1") (pintype "passive"))
      (node (ref "C17") (pin "2") (pinfunction "2_2") (pintype "passive"))
      (node (ref "C18") (pin "1") (pinfunction "1_1") (pintype "passive"))
      (node (ref "C19") (pin "1") (pinfunction "1_1") (pintype "passive"))
      (node (ref "C2") (pin "2") (pinfunction "2_2") (pintype "passive"))
      (node (ref "C20") (pin "1") (pinfunction "1_1") (pintype "passive"))
      (node (ref "C3") (pin "1") (pinfunction "1_1") (pintype "passive"))
      (node (ref "C4") (pin "2") (pinfunction "2_2") (pintype "passive"))
      (node (ref "C5") (pin "1") (pinfunction "1_1") (pintype "passive"))
      (node (ref "C6") (pin "1") (pinfunction "1_1") (pintype "passive"))
      (node (ref "C7") (pin "1") (pinfunction "1_1") (pintype "passive"))
      (node (ref "C8") (pin "1") (pinfunction "1_1") (pintype "passive"))
      (node (ref "C9") (pin "1") (pinfunction "1_1") (pintype "passive"))
      (node (ref "J1") (pin "10") (pinfunction "SHIELD_10") (pintype "passive"))
      (node (ref "J1") (pin "11") (pinfunction "SHIELD_11") (pintype "passive"))
      (node (ref "J1") (pin "12") (pinfunction "SHIELD_12") (pintype "passive"))
      (node (ref "J1") (pin "13") (pinfunction "SHIELD_13") (pintype "passive"))
      (node (ref "J1") (pin "6") (pinfunction "VSS_6") (pintype "passive"))
      (node (ref "J2") (pin "1") (pinfunction "1_1") (pintype "passive"))
      (node (ref "J2") (pin "20") (pinfunction "20_20") (pintype "passive"))
      (node (ref "J3") (pin "1") (pinfunction "1_1") (pintype "passive"))
      (node (ref "J3") (pin "20") (pinfunction "20_20") (pintype "passive"))
      (node (ref "J4") (pin "A1-B12") (pinfunction "GND_A1-B12") (pintype "power_in"))
      (node (ref "J4") (pin "B1-A12") (pinfunction "GND_B1-A12") (pintype "power_in"))
      (node (ref "J5") (pin "2") (pinfunction "2_2") (pintype "passive"))
      (node (ref "J6") (pin "11") (pinfunction "GNDDetect_11") (pintype "passive"))
      (node (ref "J6") (pin "5") (pinfunction "GND_5") (pintype "passive"))
      (node (ref "J6") (pin "7") (pinfunction "GND_7") (pintype "passive"))
      (node (ref "R10") (pin "1") (pinfunction "1_1") (pintype "passive"))
      (node (ref "R11") (pin "1") (pinfunction "1_1") (pintype "passive"))
      (node (ref "R12") (pin "1") (pinfunction "1_1") (pintype "passive"))
      (node (ref "R14") (pin "1") (pinfunction "1_1") (pintype "passive"))
      (node (ref "R8") (pin "1") (pinfunction "1_1") (pintype "passive"))
      (node (ref "SW1") (pin "1") (pinfunction "1_1") (pintype "passive"))
      (node (ref "SW1") (pin "2") (pinfunction "2_2") (pintype "passive"))
      (node (ref "SW1") (pin "5") (pinfunction "GND_5") (pintype "passive"))
      (node (ref "SW2") (pin "1") (pinfunction "1_1") (pintype "passive"))
      (node (ref "SW2") (pin "2") (pinfunction "2_2") (pintype "passive"))
      (node (ref "SW2") (pin "5") (pinfunction "GND_5") (pintype "passive"))
      (node (ref "TP5") (pin "1") (pinfunction "TP_1") (pintype "passive"))
      (node (ref "U1") (pin "23") (pinfunction "VSS_23") (pintype "passive"))
      (node (ref "U1") (pin "35") (pinfunction "VSS_35") (pintype "passive"))
      (node (ref "U1") (pin "47") (pinfunction "VSS_47") (pintype "passive"))
      (node (ref "U1") (pin "8") (pinfunction "VSSA/VREF-_8") (pintype "passive"))
      (node (ref "U2") (pin "2") (pinfunction "VSS_2") (pintype "passive"))
      (node (ref "U3") (pin "2") (pinfunction "GND_2") (pintype "passive"))
    )
    (net (code "41") (name "Net-(D1-K)") (class "Default")
      (node (ref "D1") (pin "1") (pinfunction "K_1") (pintype "passive"))
      (node (ref "R13") (pin "1") (pinfunction "1_1") (pintype "passive"))
    )
    (net (code "42") (name "Net-(D2-K)") (class "Default")
      (node (ref "C18") (pin "2") (pinfunction "2_2") (pintype "passive"))
      (node (ref "D2") (pin "1") (pinfunction "K_1") (pintype "passive"))
      (node (ref "Q1") (pin "D") (pinfunction "D_D") (pintype "passive"))
      (node (ref "U3") (pin "1") (pinfunction "VIN_1") (pintype "passive"))
      (node (ref "U3") (pin "3") (pinfunction "EN_3") (pintype "passive"))
    )
    (net (code "43") (name "Net-(J1-CARD_DETECT)") (class "Default")
      (node (ref "J1") (pin "9") (pinfunction "CARD_DETECT_9") (pintype "passive"))
      (node (ref "R5") (pin "1") (pinfunction "1_1") (pintype "passive"))
    )
    (net (code "44") (name "Net-(J4-CC1)") (class "Default")
      (node (ref "J4") (pin "A5") (pinfunction "CC1_A5") (pintype "passive"))
      (node (ref "R11") (pin "2") (pinfunction "2_2") (pintype "passive"))
    )
    (net (code "45") (name "Net-(J4-CC2)") (class "Default")
      (node (ref "J4") (pin "B5") (pinfunction "CC2_B5") (pintype "passive"))
      (node (ref "R10") (pin "2") (pinfunction "2_2") (pintype "passive"))
    )
    (net (code "46") (name "Net-(R9-Pad1)") (class "Default")
      (node (ref "R9") (pin "1") (pinfunction "1_1") (pintype "passive"))
      (node (ref "SW2") (pin "3") (pinfunction "3_3") (pintype "passive"))
      (node (ref "SW2") (pin "4") (pinfunction "4_4") (pintype "passive"))
    )
    (net (code "47") (name "Net-(U1A-PC14-OSC32_IN)") (class "Default")
      (node (ref "C5") (pin "2") (pinfunction "2_2") (pintype "passive"))
      (node (ref "U1") (pin "3") (pinfunction "PC14-OSC32_IN_3") (pintype "passive"))
      (node (ref "X2") (pin "2") (pinfunction "2_2") (pintype "passive"))
    )
    (net (code "48") (name "Net-(U1A-PC15-OSC32_OUT)") (class "Default")
      (node (ref "C6") (pin "2") (pinfunction "2_2") (pintype "passive"))
      (node (ref "U1") (pin "4") (pinfunction "PC15-OSC32_OUT_4") (pintype "passive"))
      (node (ref "X2") (pin "1") (pinfunction "1_1") (pintype "passive"))
    )
    (net (code "49") (name "Net-(U1A-PH0-OSC_IN)") (class "Default")
      (node (ref "C2") (pin "1") (pinfunction "1_1") (pintype "passive"))
      (node (ref "U1") (pin "5") (pinfunction "PH0-OSC_IN_5") (pintype "passive"))
      (node (ref "X1") (pin "1") (pinfunction "XTAL1_1") (pintype "passive"))
    )
    (net (code "50") (name "Net-(U1A-PH1-OSC_OUT)") (class "Default")
      (node (ref "C4") (pin "1") (pinfunction "1_1") (pintype "passive"))
      (node (ref "U1") (pin "6") (pinfunction "PH1-OSC_OUT_6") (pintype "passive"))
      (node (ref "X1") (pin "3") (pinfunction "XTAL2_3") (pintype "passive"))
    )
    (net (code "51") (name "Net-(U2-PROG)") (class "Default")
      (node (ref "R12") (pin "2") (pinfunction "2_2") (pintype "passive"))
      (node (ref "U2") (pin "5") (pinfunction "PROG_5") (pintype "passive"))
    )
    (net (code "52") (name "Net-(U2-STAT)") (class "Default")
      (node (ref "R13") (pin "2") (pinfunction "2_2") (pintype "passive"))
      (node (ref "U2") (pin "1") (pinfunction "STAT_1") (pintype "passive"))
    )
    (net (code "53") (name "VDDA") (class "Default")
      (node (ref "C16") (pin "2") (pinfunction "2_2") (pintype "passive"))
      (node (ref "C17") (pin "1") (pinfunction "1_1") (pintype "passive"))
      (node (ref "FB1") (pin "2") (pinfunction "2_2") (pintype "passive"))
      (node (ref "J3") (pin "3") (pinfunction "3_3") (pintype "passive"))
      (node (ref "TP4") (pin "1") (pinfunction "TP_1") (pintype "passive"))
      (node (ref "U1") (pin "9") (pinfunction "VDDA/VREF+_9") (pintype "passive"))
    )
    (net (code "54") (name "unconnected-(J1-DAT1-Pad8)") (class "Default")
      (node (ref "J1") (pin "8") (pinfunction "DAT1_8") (pintype "passive+no_connect"))
    )
    (net (code "55") (name "unconnected-(J1-DAT2-Pad1)") (class "Default")
      (node (ref "J1") (pin "1") (pinfunction "DAT2_1") (pintype "passive+no_connect"))
    )
    (net (code "56") (name "unconnected-(J4-MNT_1-Pad1)") (class "Default")
      (node (ref "J4") (pin "1") (pinfunction "MNT_1_1") (pintype "passive+no_connect"))
    )
    (net (code "57") (name "unconnected-(J4-MNT_2-Pad2)") (class "Default")
      (node (ref "J4") (pin "2") (pinfunction "MNT_2_2") (pintype "passive+no_connect"))
    )
    (net (code "58") (name "unconnected-(J4-MNT_3-Pad3)") (class "Default")
      (node (ref "J4") (pin "3") (pinfunction "MNT_3_3") (pintype "passive+no_connect"))
    )
    (net (code "59") (name "unconnected-(J4-MNT_4-Pad4)") (class "Default")
      (node (ref "J4") (pin "4") (pinfunction "MNT_4_4") (pintype "passive+no_connect"))
    )
    (net (code "60") (name "unconnected-(J4-SBU1-PadA8)") (class "Default")
      (node (ref "J4") (pin "A8") (pinfunction "SBU1_A8") (pintype "passive+no_connect"))
    )
    (net (code "61") (name "unconnected-(J4-SBU2-PadB8)") (class "Default")
      (node (ref "J4") (pin "B8") (pinfunction "SBU2_B8") (pintype "passive+no_connect"))
    )
    (net (code "62") (name "unconnected-(J5-MNT-PadMNT1)") (class "Default")
      (node (ref "J5") (pin "MNT1") (pinfunction "MNT_MNT1") (pintype "passive+no_connect"))
    )
    (net (code "63") (name "unconnected-(J5-MNT-PadMNT2)") (class "Default")
      (node (ref "J5") (pin "MNT2") (pinfunction "MNT_MNT2") (pintype "passive+no_connect"))
    )
    (net (code "64") (name "unconnected-(J6-NC-Pad9)") (class "Default")
      (node (ref "J6") (pin "9") (pinfunction "NC_9") (pintype "passive+no_connect"))
    )
    (net (code "65") (name "unconnected-(J6-NC-Pad10)") (class "Default")
      (node (ref "J6") (pin "10") (pinfunction "NC_10") (pintype "passive+no_connect"))
    )
    (net (code "66") (name "unconnected-(J6-RESV-Pad1)") (class "Default")
      (node (ref "J6") (pin "1") (pinfunction "RESV_1") (pintype "passive+no_connect"))
    )
    (net (code "67") (name "unconnected-(J6-RESV-Pad2)") (class "Default")
      (node (ref "J6") (pin "2") (pinfunction "RESV_2") (pintype "passive+no_connect"))
    )
    (net (code "68") (name "unconnected-(PTH1-H1-Pad1)") (class "Default")
      (node (ref "PTH1") (pin "1") (pinfunction "H1_1") (pintype "passive+no_connect"))
    )
    (net (code "69") (name "unconnected-(PTH2-H1-Pad1)") (class "Default")
      (node (ref "PTH2") (pin "1") (pinfunction "H1_1") (pintype "passive+no_connect"))
    )
    (net (code "70") (name "unconnected-(PTH3-H1-Pad1)") (class "Default")
      (node (ref "PTH3") (pin "1") (pinfunction "H1_1") (pintype "passive+no_connect"))
    )
    (net (code "71") (name "unconnected-(PTH4-H1-Pad1)") (class "Default")
      (node (ref "PTH4") (pin "1") (pinfunction "H1_1") (pintype "passive+no_connect"))
    )
    (net (code "72") (name "unconnected-(U3-NC-Pad4)") (class "Default")
      (node (ref "U3") (pin "4") (pinfunction "NC_4") (pintype "passive+no_connect"))
    )
    (net (code "73") (name "unconnected-(X1-GND-Pad2)") (class "Default")
      (node (ref "X1") (pin "2") (pinfunction "GND_2") (pintype "passive+no_connect"))
    )
    (net (code "74") (name "unconnected-(X1-GND-Pad4)") (class "Default")
      (node (ref "X1") (pin "4") (pinfunction "GND_4") (pintype "passive+no_connect"))
    )
  )
)
